# ERobot_Minimalis_-_2023.net
KiCad netlist of a schematic drawn in EAGLE
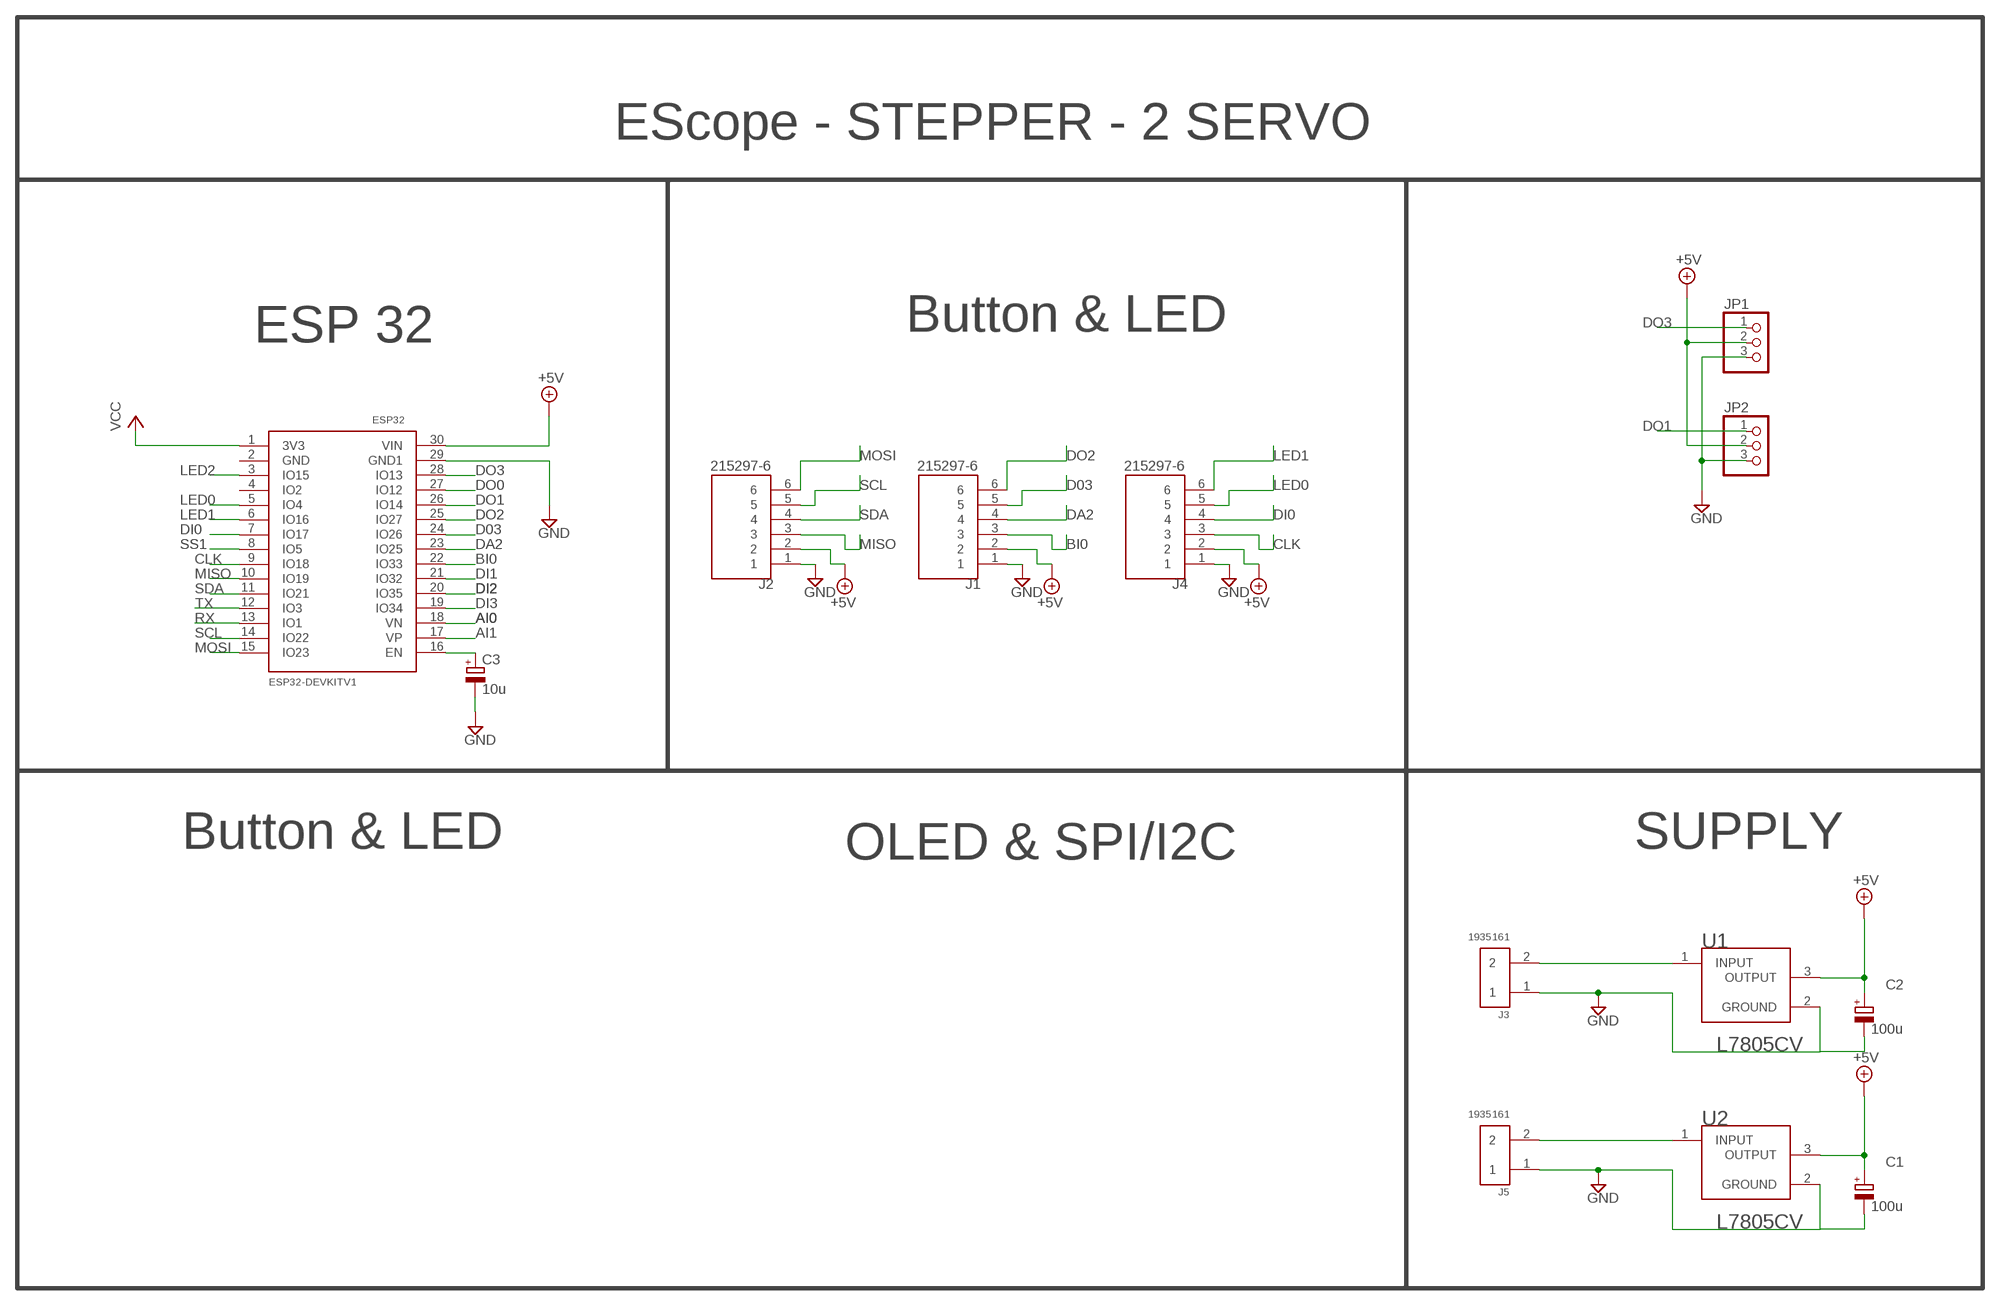
[diagram p0: schematic, sheet 1]

(export (version "E")
  (design (tool "Eeschema 10.0.6"))
  (components
    (comp (ref "C1")
      (value "100u")
      (footprint "eagle-import:E3,5-8")
      (libsource (lib "eagle-import") (part "CPOL-EUE3.5-8"))
    )
    (comp (ref "C2")
      (value "100u")
      (footprint "eagle-import:E3,5-8")
      (libsource (lib "eagle-import") (part "CPOL-EUE3.5-8"))
    )
    (comp (ref "C3")
      (value "10u")
      (footprint "eagle-import:E2,5-5")
      (libsource (lib "eagle-import") (part "CPOL-EUE2.5-5"))
    )
    (comp (ref "ESP32")
      (value "DEVKIT-V1")
      (footprint "eagle-import:ESP32-DEVKITV1")
      (libsource (lib "eagle-import") (part "ESP32DEVKITV1"))
    )
    (comp (ref "J1")
      (value "215297-6")
      (footprint "eagle-import:TE_215297-6")
      (fields (field (name "MF") "TE Connectivity"))
      (libsource (lib "eagle-import") (part "215297-6"))
    )
    (comp (ref "J2")
      (value "215297-6")
      (footprint "eagle-import:TE_215297-6")
      (fields (field (name "MF") "TE Connectivity"))
      (libsource (lib "eagle-import") (part "215297-6"))
    )
    (comp (ref "J3")
      (value "1935161")
      (footprint "eagle-import:PHOENIX_1935161")
      (fields (field (name "MF") "Phoenix Contact"))
      (libsource (lib "eagle-import") (part "1935161"))
    )
    (comp (ref "J4")
      (value "215297-6")
      (footprint "eagle-import:TE_215297-6")
      (fields (field (name "MF") "TE Connectivity"))
      (libsource (lib "eagle-import") (part "215297-6"))
    )
    (comp (ref "J5")
      (value "1935161")
      (footprint "eagle-import:PHOENIX_1935161")
      (fields (field (name "MF") "Phoenix Contact"))
      (libsource (lib "eagle-import") (part "1935161"))
    )
    (comp (ref "JP1")
      (value "PINHD-1X3")
      (footprint "eagle-import:1X03")
      (libsource (lib "eagle-import") (part "PINHD-1X3"))
    )
    (comp (ref "JP2")
      (value "PINHD-1X3")
      (footprint "eagle-import:1X03")
      (libsource (lib "eagle-import") (part "PINHD-1X3"))
    )
    (comp (ref "U1")
      (value "STMICROELECTRONICS_L7805CVSTMICROELECTRONICS_L7805CV_0_0")
      (footprint "eagle-import:STMICROELECTRONICS_L7805CV_0")
      (fields
        (field (name "DIGIKEY_PART_NUMBER") "497-1443-5-ND")
        (field (name "MF") "STMicroelectronics")
        (field (name "MOUSER_PART_NUMBER") "511-L7805CV")
      )
      (libsource (lib "eagle-import") (part "STMICROELECTRONICS_L7805CVSTMICROELECTRONICS_L7805CV_0_0"))
    )
    (comp (ref "U2")
      (value "STMICROELECTRONICS_L7805CVSTMICROELECTRONICS_L7805CV_0_0")
      (footprint "eagle-import:STMICROELECTRONICS_L7805CV_0")
      (fields
        (field (name "DIGIKEY_PART_NUMBER") "497-1443-5-ND")
        (field (name "MF") "STMicroelectronics")
        (field (name "MOUSER_PART_NUMBER") "511-L7805CV")
      )
      (libsource (lib "eagle-import") (part "STMICROELECTRONICS_L7805CVSTMICROELECTRONICS_L7805CV_0_0"))
    )
  )
  (nets
    (net (code "1") (name "+5V") (class "Default")
      (node (ref "C1") (pin "+") (pinfunction "+_+") (pintype "passive"))
      (node (ref "C2") (pin "+") (pinfunction "+_+") (pintype "passive"))
      (node (ref "ESP32") (pin "30") (pinfunction "VIN_30") (pintype "bidirectional"))
      (node (ref "J1") (pin "2") (pinfunction "2_2") (pintype "passive"))
      (node (ref "J2") (pin "2") (pinfunction "2_2") (pintype "passive"))
      (node (ref "J4") (pin "2") (pinfunction "2_2") (pintype "passive"))
      (node (ref "JP1") (pin "2") (pinfunction "2_2") (pintype "passive"))
      (node (ref "JP2") (pin "2") (pinfunction "2_2") (pintype "passive"))
      (node (ref "U1") (pin "3") (pinfunction "OUTPUT_3") (pintype "bidirectional"))
      (node (ref "U2") (pin "3") (pinfunction "OUTPUT_3") (pintype "bidirectional"))
    )
    (net (code "2") (name "/AI0") (class "Default")
      (node (ref "ESP32") (pin "18") (pinfunction "VN_18") (pintype "bidirectional"))
    )
    (net (code "3") (name "/AI1") (class "Default")
      (node (ref "ESP32") (pin "17") (pinfunction "VP_17") (pintype "bidirectional"))
    )
    (net (code "4") (name "/BI0") (class "Default")
      (node (ref "ESP32") (pin "22") (pinfunction "IO33_22") (pintype "bidirectional"))
      (node (ref "J1") (pin "3") (pinfunction "3_3") (pintype "passive"))
    )
    (net (code "5") (name "/CLK") (class "Default")
      (node (ref "ESP32") (pin "9") (pinfunction "IO18_9") (pintype "bidirectional"))
      (node (ref "J4") (pin "3") (pinfunction "3_3") (pintype "passive"))
    )
    (net (code "6") (name "/D03") (class "Default")
      (node (ref "ESP32") (pin "24") (pinfunction "IO26_24") (pintype "bidirectional"))
      (node (ref "J1") (pin "5") (pinfunction "5_5") (pintype "passive"))
    )
    (net (code "7") (name "/DA2") (class "Default")
      (node (ref "ESP32") (pin "23") (pinfunction "IO25_23") (pintype "bidirectional"))
      (node (ref "J1") (pin "4") (pinfunction "4_4") (pintype "passive"))
    )
    (net (code "8") (name "/DI0") (class "Default")
      (node (ref "ESP32") (pin "7") (pinfunction "IO17_7") (pintype "bidirectional"))
      (node (ref "J4") (pin "4") (pinfunction "4_4") (pintype "passive"))
    )
    (net (code "9") (name "/DI1") (class "Default")
      (node (ref "ESP32") (pin "21") (pinfunction "IO32_21") (pintype "bidirectional"))
    )
    (net (code "10") (name "/DI2") (class "Default")
      (node (ref "ESP32") (pin "20") (pinfunction "IO35_20") (pintype "bidirectional"))
    )
    (net (code "11") (name "/DI3") (class "Default")
      (node (ref "ESP32") (pin "19") (pinfunction "IO34_19") (pintype "bidirectional"))
    )
    (net (code "12") (name "/DO0") (class "Default")
      (node (ref "ESP32") (pin "27") (pinfunction "IO12_27") (pintype "bidirectional"))
    )
    (net (code "13") (name "/DO1") (class "Default")
      (node (ref "ESP32") (pin "26") (pinfunction "IO14_26") (pintype "bidirectional"))
      (node (ref "JP2") (pin "1") (pinfunction "1_1") (pintype "passive"))
    )
    (net (code "14") (name "/DO2") (class "Default")
      (node (ref "ESP32") (pin "25") (pinfunction "IO27_25") (pintype "bidirectional"))
      (node (ref "J1") (pin "6") (pinfunction "6_6") (pintype "passive"))
    )
    (net (code "15") (name "/DO3") (class "Default")
      (node (ref "ESP32") (pin "28") (pinfunction "IO13_28") (pintype "bidirectional"))
      (node (ref "JP1") (pin "1") (pinfunction "1_1") (pintype "passive"))
    )
    (net (code "16") (name "/LED0") (class "Default")
      (node (ref "ESP32") (pin "5") (pinfunction "IO4_5") (pintype "bidirectional"))
      (node (ref "J4") (pin "5") (pinfunction "5_5") (pintype "passive"))
    )
    (net (code "17") (name "/LED1") (class "Default")
      (node (ref "ESP32") (pin "6") (pinfunction "IO16_6") (pintype "bidirectional"))
      (node (ref "J4") (pin "6") (pinfunction "6_6") (pintype "passive"))
    )
    (net (code "18") (name "/LED2") (class "Default")
      (node (ref "ESP32") (pin "3") (pinfunction "IO15_3") (pintype "bidirectional"))
    )
    (net (code "19") (name "/MISO") (class "Default")
      (node (ref "ESP32") (pin "10") (pinfunction "IO19_10") (pintype "bidirectional"))
      (node (ref "J2") (pin "3") (pinfunction "3_3") (pintype "passive"))
    )
    (net (code "20") (name "/MOSI") (class "Default")
      (node (ref "ESP32") (pin "15") (pinfunction "IO23_15") (pintype "bidirectional"))
      (node (ref "J2") (pin "6") (pinfunction "6_6") (pintype "passive"))
    )
    (net (code "21") (name "/RX") (class "Default")
      (node (ref "ESP32") (pin "13") (pinfunction "IO1_13") (pintype "bidirectional"))
    )
    (net (code "22") (name "/SCL") (class "Default")
      (node (ref "ESP32") (pin "14") (pinfunction "IO22_14") (pintype "bidirectional"))
      (node (ref "J2") (pin "5") (pinfunction "5_5") (pintype "passive"))
    )
    (net (code "23") (name "/SDA") (class "Default")
      (node (ref "ESP32") (pin "11") (pinfunction "IO21_11") (pintype "bidirectional"))
      (node (ref "J2") (pin "4") (pinfunction "4_4") (pintype "passive"))
    )
    (net (code "24") (name "/SS1") (class "Default")
      (node (ref "ESP32") (pin "8") (pinfunction "IO5_8") (pintype "bidirectional"))
    )
    (net (code "25") (name "/TX") (class "Default")
      (node (ref "ESP32") (pin "12") (pinfunction "IO3_12") (pintype "bidirectional"))
    )
    (net (code "26") (name "GND") (class "Default")
      (node (ref "C1") (pin "-") (pinfunction "-_-") (pintype "passive"))
      (node (ref "C2") (pin "-") (pinfunction "-_-") (pintype "passive"))
      (node (ref "C3") (pin "-") (pinfunction "-_-") (pintype "passive"))
      (node (ref "ESP32") (pin "29") (pinfunction "GND1_29") (pintype "bidirectional"))
      (node (ref "J1") (pin "1") (pinfunction "1_1") (pintype "passive"))
      (node (ref "J2") (pin "1") (pinfunction "1_1") (pintype "passive"))
      (node (ref "J3") (pin "1") (pinfunction "1_1") (pintype "passive"))
      (node (ref "J4") (pin "1") (pinfunction "1_1") (pintype "passive"))
      (node (ref "J5") (pin "1") (pinfunction "1_1") (pintype "passive"))
      (node (ref "JP1") (pin "3") (pinfunction "3_3") (pintype "passive"))
      (node (ref "JP2") (pin "3") (pinfunction "3_3") (pintype "passive"))
      (node (ref "U1") (pin "2") (pinfunction "GROUND_2") (pintype "bidirectional"))
      (node (ref "U2") (pin "2") (pinfunction "GROUND_2") (pintype "bidirectional"))
    )
    (net (code "27") (name "Net-(ESP32-EN)") (class "Default")
      (node (ref "C3") (pin "+") (pinfunction "+_+") (pintype "passive"))
      (node (ref "ESP32") (pin "16") (pinfunction "EN_16") (pintype "bidirectional"))
    )
    (net (code "28") (name "Net-(U1-INPUT)") (class "Default")
      (node (ref "J3") (pin "2") (pinfunction "2_2") (pintype "passive"))
      (node (ref "U1") (pin "1") (pinfunction "INPUT_1") (pintype "bidirectional"))
    )
    (net (code "29") (name "Net-(U2-INPUT)") (class "Default")
      (node (ref "J5") (pin "2") (pinfunction "2_2") (pintype "passive"))
      (node (ref "U2") (pin "1") (pinfunction "INPUT_1") (pintype "bidirectional"))
    )
    (net (code "30") (name "VCC") (class "Default")
      (node (ref "ESP32") (pin "1") (pinfunction "3V3_1") (pintype "bidirectional"))
    )
    (net (code "31") (name "unconnected-(ESP32-GND-Pad2)") (class "Default")
      (node (ref "ESP32") (pin "2") (pinfunction "GND_2") (pintype "bidirectional"))
    )
    (net (code "32") (name "unconnected-(ESP32-IO2-Pad4)") (class "Default")
      (node (ref "ESP32") (pin "4") (pinfunction "IO2_4") (pintype "bidirectional"))
    )
  )
)
